# Encoder.net
KiCad netlist of a schematic drawn in Altium Designer
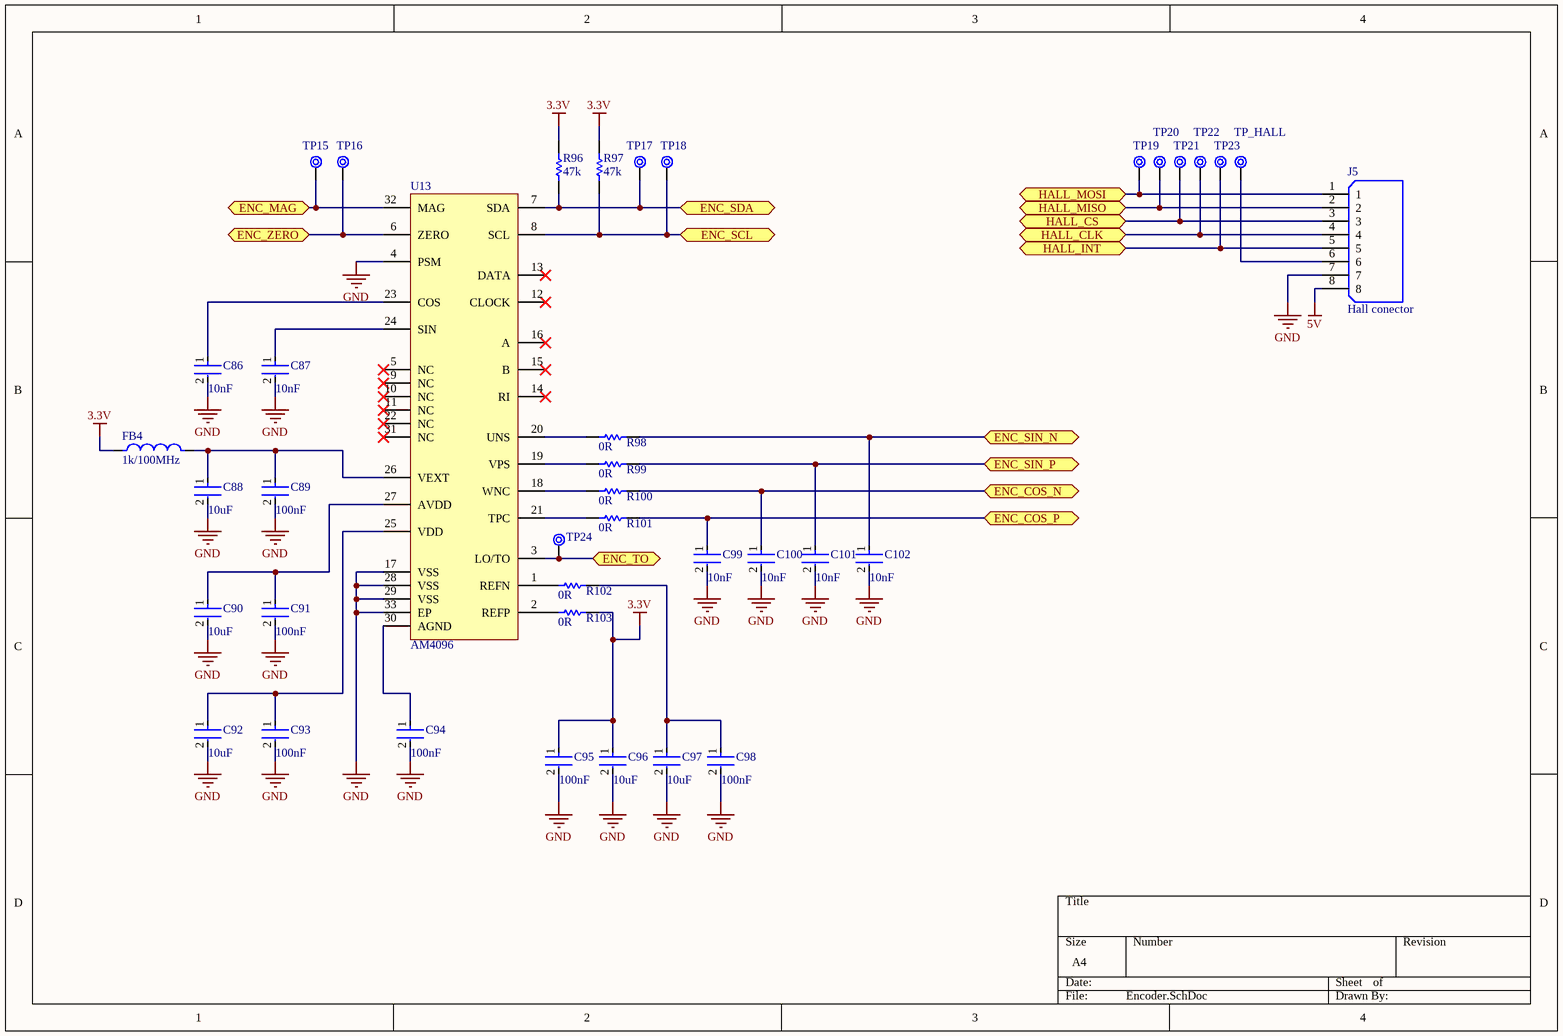
[diagram p0: Encoder.SchDoc]

(export (version "E")
  (design (tool "Eeschema 10.0.6"))
  (components
    (comp (ref "C86")
      (value "10nF")
      (footprint "FP-C0805C-DN-MFG")
      (description "CAP CER 0.1UF 50V X7R 0805")
      (fields
        (field (name "MANUFACTURER PART NUMBER") "C0805C104K5RACTU")
        (field (name "MANUFACTURER") "KEMET")
      )
      (libsource (lib "Altium Content Vault") (part "b4654b650e69147ec39a6b967a45e02"))
    )
    (comp (ref "C87")
      (value "10nF")
      (footprint "FP-C0805C-DN-MFG")
      (description "CAP CER 0.1UF 50V X7R 0805")
      (fields
        (field (name "MANUFACTURER PART NUMBER") "C0805C104K5RACTU")
        (field (name "MANUFACTURER") "KEMET")
      )
      (libsource (lib "Altium Content Vault") (part "b4654b650e69147ec39a6b967a45e02"))
    )
    (comp (ref "C88")
      (value "10uF")
      (footprint "FP-C0805C-DN-MFG")
      (description "CAP CER 0.1UF 50V X7R 0805")
      (fields
        (field (name "MANUFACTURER PART NUMBER") "C0805C104K5RACTU")
        (field (name "MANUFACTURER") "KEMET")
      )
      (libsource (lib "Altium Content Vault") (part "b4654b650e69147ec39a6b967a45e02"))
    )
    (comp (ref "C89")
      (value "100nF")
      (footprint "FP-C0805C-DN-MFG")
      (description "CAP CER 0.1UF 50V X7R 0805")
      (fields
        (field (name "MANUFACTURER PART NUMBER") "C0805C104K5RACTU")
        (field (name "MANUFACTURER") "KEMET")
      )
      (libsource (lib "Altium Content Vault") (part "b4654b650e69147ec39a6b967a45e02"))
    )
    (comp (ref "C90")
      (value "10uF")
      (footprint "FP-C0805C-DN-MFG")
      (description "CAP CER 0.1UF 50V X7R 0805")
      (fields
        (field (name "MANUFACTURER PART NUMBER") "C0805C104K5RACTU")
        (field (name "MANUFACTURER") "KEMET")
      )
      (libsource (lib "Altium Content Vault") (part "b4654b650e69147ec39a6b967a45e02"))
    )
    (comp (ref "C91")
      (value "100nF")
      (footprint "FP-C0805C-DN-MFG")
      (description "CAP CER 0.1UF 50V X7R 0805")
      (fields
        (field (name "MANUFACTURER PART NUMBER") "C0805C104K5RACTU")
        (field (name "MANUFACTURER") "KEMET")
      )
      (libsource (lib "Altium Content Vault") (part "b4654b650e69147ec39a6b967a45e02"))
    )
    (comp (ref "C92")
      (value "10uF")
      (footprint "FP-C0805C-DN-MFG")
      (description "CAP CER 0.1UF 50V X7R 0805")
      (fields
        (field (name "MANUFACTURER PART NUMBER") "C0805C104K5RACTU")
        (field (name "MANUFACTURER") "KEMET")
      )
      (libsource (lib "Altium Content Vault") (part "b4654b650e69147ec39a6b967a45e02"))
    )
    (comp (ref "C93")
      (value "100nF")
      (footprint "FP-C0805C-DN-MFG")
      (description "CAP CER 0.1UF 50V X7R 0805")
      (fields
        (field (name "MANUFACTURER PART NUMBER") "C0805C104K5RACTU")
        (field (name "MANUFACTURER") "KEMET")
      )
      (libsource (lib "Altium Content Vault") (part "b4654b650e69147ec39a6b967a45e02"))
    )
    (comp (ref "C94")
      (value "100nF")
      (footprint "FP-C0805C-DN-MFG")
      (description "CAP CER 0.1UF 50V X7R 0805")
      (fields
        (field (name "MANUFACTURER PART NUMBER") "C0805C104K5RACTU")
        (field (name "MANUFACTURER") "KEMET")
      )
      (libsource (lib "Altium Content Vault") (part "b4654b650e69147ec39a6b967a45e02"))
    )
    (comp (ref "C95")
      (value "100nF")
      (footprint "FP-C0805C-DN-MFG")
      (description "CAP CER 0.1UF 50V X7R 0805")
      (fields
        (field (name "MANUFACTURER PART NUMBER") "C0805C104K5RACTU")
        (field (name "MANUFACTURER") "KEMET")
      )
      (libsource (lib "Altium Content Vault") (part "b4654b650e69147ec39a6b967a45e02"))
    )
    (comp (ref "C96")
      (value "10uF")
      (footprint "FP-C0805C-DN-MFG")
      (description "CAP CER 0.1UF 50V X7R 0805")
      (fields
        (field (name "MANUFACTURER PART NUMBER") "C0805C104K5RACTU")
        (field (name "MANUFACTURER") "KEMET")
      )
      (libsource (lib "Altium Content Vault") (part "b4654b650e69147ec39a6b967a45e02"))
    )
    (comp (ref "C97")
      (value "10uF")
      (footprint "FP-C0805C-DN-MFG")
      (description "CAP CER 0.1UF 50V X7R 0805")
      (fields
        (field (name "MANUFACTURER PART NUMBER") "C0805C104K5RACTU")
        (field (name "MANUFACTURER") "KEMET")
      )
      (libsource (lib "Altium Content Vault") (part "b4654b650e69147ec39a6b967a45e02"))
    )
    (comp (ref "C98")
      (value "100nF")
      (footprint "FP-C0805C-DN-MFG")
      (description "CAP CER 0.1UF 50V X7R 0805")
      (fields
        (field (name "MANUFACTURER PART NUMBER") "C0805C104K5RACTU")
        (field (name "MANUFACTURER") "KEMET")
      )
      (libsource (lib "Altium Content Vault") (part "b4654b650e69147ec39a6b967a45e02"))
    )
    (comp (ref "C99")
      (value "10nF")
      (footprint "FP-C0805C-DN-MFG")
      (description "CAP CER 0.1UF 50V X7R 0805")
      (fields
        (field (name "MANUFACTURER PART NUMBER") "C0805C104K5RACTU")
        (field (name "MANUFACTURER") "KEMET")
      )
      (libsource (lib "Altium Content Vault") (part "b4654b650e69147ec39a6b967a45e02"))
    )
    (comp (ref "C100")
      (value "10nF")
      (footprint "FP-C0805C-DN-MFG")
      (description "CAP CER 0.1UF 50V X7R 0805")
      (fields
        (field (name "MANUFACTURER PART NUMBER") "C0805C104K5RACTU")
        (field (name "MANUFACTURER") "KEMET")
      )
      (libsource (lib "Altium Content Vault") (part "b4654b650e69147ec39a6b967a45e02"))
    )
    (comp (ref "C101")
      (value "10nF")
      (footprint "FP-C0805C-DN-MFG")
      (description "CAP CER 0.1UF 50V X7R 0805")
      (fields
        (field (name "MANUFACTURER PART NUMBER") "C0805C104K5RACTU")
        (field (name "MANUFACTURER") "KEMET")
      )
      (libsource (lib "Altium Content Vault") (part "b4654b650e69147ec39a6b967a45e02"))
    )
    (comp (ref "C102")
      (value "10nF")
      (footprint "FP-C0805C-DN-MFG")
      (description "CAP CER 0.1UF 50V X7R 0805")
      (fields
        (field (name "MANUFACTURER PART NUMBER") "C0805C104K5RACTU")
        (field (name "MANUFACTURER") "KEMET")
      )
      (libsource (lib "Altium Content Vault") (part "b4654b650e69147ec39a6b967a45e02"))
    )
    (comp (ref "FB4")
      (value "1k/100MHz")
      (footprint "FB_0603")
      (description "Ferrite Beads 1K OHM 25%")
      (fields (field (name "MANUFACTURER") "TDK") (field (name "PART NUMBER") "MMZ1608B102CTA00"))
      (libsource (lib "INDUCTOR") (part "FB/MMZ1608B102CTA00"))
    )
    (comp (ref "J5")
      (value "Hall conector")
      (footprint "AMPHENOL_10114830-11108LF")
      (description "1.25mm Wire to Board Wafer, Right Angle, Surface Mount, 8 Positions")
      (fields (field (name "MF") "Amphenol ICC") (field (name "MP") "10114830-11108LF"))
      (libsource (lib "10114830-11108LF") (part "10114830-11108LF"))
    )
    (comp (ref "R96")
      (value "47k")
      (footprint "RESC2013X50X30LL20T20")
      (fields (field (name "MANUFACTURER") "Vishay Dale") (field (name "PART NUMBER") "CRCW08050000Z0EA"))
      (libsource (lib "Altium Content Vault") (part "RES"))
    )
    (comp (ref "R97")
      (value "47k")
      (footprint "RESC2013X50X30LL20T20")
      (fields (field (name "MANUFACTURER") "Vishay Dale") (field (name "PART NUMBER") "CRCW08050000Z0EA"))
      (libsource (lib "Altium Content Vault") (part "RES"))
    )
    (comp (ref "R98")
      (value "0R")
      (footprint "RESC1609X50X30NL8T20")
      (description "Chip Resistor, 0 Ohm, Jumper, 100 mW, -55 to 155 degC, 0603 (1608 Metric), RoHS, Tape and Reel")
      (fields (field (name "MANUFACTURER") "Vishay Semiconductor"))
      (libsource (lib "Altium Content Vault") (part "RES-2"))
    )
    (comp (ref "R99")
      (value "0R")
      (footprint "RESC1609X50X30NL8T20")
      (description "Chip Resistor, 0 Ohm, Jumper, 100 mW, -55 to 155 degC, 0603 (1608 Metric), RoHS, Tape and Reel")
      (fields (field (name "MANUFACTURER") "Vishay Semiconductor"))
      (libsource (lib "Altium Content Vault") (part "RES-2"))
    )
    (comp (ref "R100")
      (value "0R")
      (footprint "RESC1609X50X30NL8T20")
      (description "Chip Resistor, 0 Ohm, Jumper, 100 mW, -55 to 155 degC, 0603 (1608 Metric), RoHS, Tape and Reel")
      (fields (field (name "MANUFACTURER") "Vishay Semiconductor"))
      (libsource (lib "Altium Content Vault") (part "RES-2"))
    )
    (comp (ref "R101")
      (value "0R")
      (footprint "RESC1609X50X30NL8T20")
      (description "Chip Resistor, 0 Ohm, Jumper, 100 mW, -55 to 155 degC, 0603 (1608 Metric), RoHS, Tape and Reel")
      (fields (field (name "MANUFACTURER") "Vishay Semiconductor"))
      (libsource (lib "Altium Content Vault") (part "RES-2"))
    )
    (comp (ref "R102")
      (value "0R")
      (footprint "RESC1609X50X30NL8T20")
      (description "Chip Resistor, 0 Ohm, Jumper, 100 mW, -55 to 155 degC, 0603 (1608 Metric), RoHS, Tape and Reel")
      (fields (field (name "MANUFACTURER") "Vishay Semiconductor"))
      (libsource (lib "Altium Content Vault") (part "RES-2"))
    )
    (comp (ref "R103")
      (value "0R")
      (footprint "RESC1609X50X30NL8T20")
      (description "Chip Resistor, 0 Ohm, Jumper, 100 mW, -55 to 155 degC, 0603 (1608 Metric), RoHS, Tape and Reel")
      (fields (field (name "MANUFACTURER") "Vishay Semiconductor"))
      (libsource (lib "Altium Content Vault") (part "RES-2"))
    )
    (comp (ref "TP15")
      (value "Test Point 1mm")
      (footprint "Pad 1mm")
      (libsource (lib "OTHER") (part "Test Point 1mm"))
    )
    (comp (ref "TP16")
      (value "Test Point 1mm")
      (footprint "Pad 1mm")
      (libsource (lib "OTHER") (part "Test Point 1mm"))
    )
    (comp (ref "TP17")
      (value "Test Point 1mm")
      (footprint "Pad 1mm")
      (libsource (lib "OTHER") (part "Test Point 1mm"))
    )
    (comp (ref "TP18")
      (value "Test Point 1mm")
      (footprint "Pad 1mm")
      (libsource (lib "OTHER") (part "Test Point 1mm"))
    )
    (comp (ref "TP19")
      (value "Test Point 1mm")
      (footprint "Pad 1mm")
      (libsource (lib "OTHER") (part "Test Point 1mm"))
    )
    (comp (ref "TP20")
      (value "Test Point 1mm")
      (footprint "Pad 1mm")
      (libsource (lib "OTHER") (part "Test Point 1mm"))
    )
    (comp (ref "TP21")
      (value "Test Point 1mm")
      (footprint "Pad 1mm")
      (libsource (lib "OTHER") (part "Test Point 1mm"))
    )
    (comp (ref "TP22")
      (value "Test Point 1mm")
      (footprint "Pad 1mm")
      (libsource (lib "OTHER") (part "Test Point 1mm"))
    )
    (comp (ref "TP23")
      (value "Test Point 1mm")
      (footprint "Pad 1mm")
      (libsource (lib "OTHER") (part "Test Point 1mm"))
    )
    (comp (ref "TP24")
      (value "Test Point 1mm")
      (footprint "Pad 1mm")
      (libsource (lib "OTHER") (part "Test Point 1mm"))
    )
    (comp (ref "TP_HALL")
      (value "Test Point 1mm")
      (footprint "Pad 1mm")
      (libsource (lib "OTHER") (part "Test Point 1mm"))
    )
    (comp (ref "U13")
      (value "AM4096")
      (footprint "QFN65P600X600X100_HS-33N")
      (description "12 bit Rotary Magnetic Encoder IC")
      (fields (field (name "MANUFACTURER") "RLS"))
      (libsource (lib "IC") (part "AM4096"))
    )
  )
  (nets
    (net (code "1") (name "/ENC_COS_N") (class "Default")
      (node (ref "C100") (pin "1") (pinfunction "1_1") (pintype "passive"))
      (node (ref "R100") (pin "2") (pinfunction "2_2") (pintype "passive"))
    )
    (net (code "2") (name "/ENC_COS_P") (class "Default")
      (node (ref "C99") (pin "1") (pinfunction "1_1") (pintype "passive"))
      (node (ref "R101") (pin "2") (pinfunction "2_2") (pintype "passive"))
    )
    (net (code "3") (name "/ENC_MAG") (class "Default")
      (node (ref "TP15") (pin "1") (pinfunction "1_1") (pintype "passive"))
      (node (ref "U13") (pin "32") (pinfunction "MAG_32") (pintype "passive"))
    )
    (net (code "4") (name "/ENC_SCL") (class "Default")
      (node (ref "R97") (pin "1") (pinfunction "1_1") (pintype "passive"))
      (node (ref "TP18") (pin "1") (pinfunction "1_1") (pintype "passive"))
      (node (ref "U13") (pin "8") (pinfunction "SCL_8") (pintype "passive"))
    )
    (net (code "5") (name "/ENC_SDA") (class "Default")
      (node (ref "R96") (pin "1") (pinfunction "1_1") (pintype "passive"))
      (node (ref "TP17") (pin "1") (pinfunction "1_1") (pintype "passive"))
      (node (ref "U13") (pin "7") (pinfunction "SDA_7") (pintype "passive"))
    )
    (net (code "6") (name "/ENC_SIN_N") (class "Default")
      (node (ref "C102") (pin "1") (pinfunction "1_1") (pintype "passive"))
      (node (ref "R98") (pin "2") (pinfunction "2_2") (pintype "passive"))
    )
    (net (code "7") (name "/ENC_SIN_P") (class "Default")
      (node (ref "C101") (pin "1") (pinfunction "1_1") (pintype "passive"))
      (node (ref "R99") (pin "2") (pinfunction "2_2") (pintype "passive"))
    )
    (net (code "8") (name "/ENC_TO") (class "Default")
      (node (ref "TP24") (pin "1") (pinfunction "1_1") (pintype "passive"))
      (node (ref "U13") (pin "3") (pinfunction "LO/TO_3") (pintype "passive"))
    )
    (net (code "9") (name "/ENC_ZERO") (class "Default")
      (node (ref "TP16") (pin "1") (pinfunction "1_1") (pintype "passive"))
      (node (ref "U13") (pin "6") (pinfunction "ZERO_6") (pintype "passive"))
    )
    (net (code "10") (name "/HALL_CLK") (class "Default")
      (node (ref "J5") (pin "4") (pinfunction "4_4") (pintype "passive"))
      (node (ref "TP22") (pin "1") (pinfunction "1_1") (pintype "passive"))
    )
    (net (code "11") (name "/HALL_CS") (class "Default")
      (node (ref "J5") (pin "3") (pinfunction "3_3") (pintype "passive"))
      (node (ref "TP21") (pin "1") (pinfunction "1_1") (pintype "passive"))
    )
    (net (code "12") (name "/HALL_INT") (class "Default")
      (node (ref "J5") (pin "5") (pinfunction "5_5") (pintype "passive"))
      (node (ref "TP23") (pin "1") (pinfunction "1_1") (pintype "passive"))
    )
    (net (code "13") (name "/HALL_MISO") (class "Default")
      (node (ref "J5") (pin "2") (pinfunction "2_2") (pintype "passive"))
      (node (ref "TP20") (pin "1") (pinfunction "1_1") (pintype "passive"))
    )
    (net (code "14") (name "/HALL_MOSI") (class "Default")
      (node (ref "J5") (pin "1") (pinfunction "1_1") (pintype "passive"))
      (node (ref "TP19") (pin "1") (pinfunction "1_1") (pintype "passive"))
    )
    (net (code "15") (name "3.3V") (class "Default")
      (node (ref "C95") (pin "1") (pinfunction "1_1") (pintype "passive"))
      (node (ref "C96") (pin "1") (pinfunction "1_1") (pintype "passive"))
      (node (ref "FB4") (pin "1") (pinfunction "1_1") (pintype "passive"))
      (node (ref "R103") (pin "2") (pinfunction "2_2") (pintype "passive"))
      (node (ref "R96") (pin "2") (pinfunction "2_2") (pintype "passive"))
      (node (ref "R97") (pin "2") (pinfunction "2_2") (pintype "passive"))
    )
    (net (code "16") (name "5V") (class "Default")
      (node (ref "J5") (pin "8") (pinfunction "8_8") (pintype "passive"))
    )
    (net (code "17") (name "GND") (class "Default")
      (node (ref "C100") (pin "2") (pinfunction "2_2") (pintype "passive"))
      (node (ref "C101") (pin "2") (pinfunction "2_2") (pintype "passive"))
      (node (ref "C102") (pin "2") (pinfunction "2_2") (pintype "passive"))
      (node (ref "C86") (pin "2") (pinfunction "2_2") (pintype "passive"))
      (node (ref "C87") (pin "2") (pinfunction "2_2") (pintype "passive"))
      (node (ref "C88") (pin "2") (pinfunction "2_2") (pintype "passive"))
      (node (ref "C89") (pin "2") (pinfunction "2_2") (pintype "passive"))
      (node (ref "C90") (pin "2") (pinfunction "2_2") (pintype "passive"))
      (node (ref "C91") (pin "2") (pinfunction "2_2") (pintype "passive"))
      (node (ref "C92") (pin "2") (pinfunction "2_2") (pintype "passive"))
      (node (ref "C93") (pin "2") (pinfunction "2_2") (pintype "passive"))
      (node (ref "C94") (pin "2") (pinfunction "2_2") (pintype "passive"))
      (node (ref "C95") (pin "2") (pinfunction "2_2") (pintype "passive"))
      (node (ref "C96") (pin "2") (pinfunction "2_2") (pintype "passive"))
      (node (ref "C97") (pin "2") (pinfunction "2_2") (pintype "passive"))
      (node (ref "C98") (pin "2") (pinfunction "2_2") (pintype "passive"))
      (node (ref "C99") (pin "2") (pinfunction "2_2") (pintype "passive"))
      (node (ref "J5") (pin "7") (pinfunction "7_7") (pintype "passive"))
      (node (ref "U13") (pin "17") (pinfunction "VSS_17") (pintype "passive"))
      (node (ref "U13") (pin "28") (pinfunction "VSS_28") (pintype "passive"))
      (node (ref "U13") (pin "29") (pinfunction "VSS_29") (pintype "passive"))
      (node (ref "U13") (pin "33") (pinfunction "EP_33") (pintype "passive"))
      (node (ref "U13") (pin "4") (pinfunction "PSM_4") (pintype "passive"))
    )
    (net (code "18") (name "Net-(C97-Pad1)") (class "Default")
      (node (ref "C97") (pin "1") (pinfunction "1_1") (pintype "passive"))
      (node (ref "C98") (pin "1") (pinfunction "1_1") (pintype "passive"))
      (node (ref "R102") (pin "2") (pinfunction "2_2") (pintype "passive"))
    )
    (net (code "19") (name "Net-(J5-Pad6)") (class "Default")
      (node (ref "J5") (pin "6") (pinfunction "6_6") (pintype "passive"))
      (node (ref "TP_HALL") (pin "1") (pinfunction "1_1") (pintype "passive"))
    )
    (net (code "20") (name "Net-(U13-AGND)") (class "Default")
      (node (ref "C94") (pin "1") (pinfunction "1_1") (pintype "passive"))
      (node (ref "U13") (pin "30") (pinfunction "AGND_30") (pintype "passive"))
    )
    (net (code "21") (name "Net-(U13-AVDD)") (class "Default")
      (node (ref "C90") (pin "1") (pinfunction "1_1") (pintype "passive"))
      (node (ref "C91") (pin "1") (pinfunction "1_1") (pintype "passive"))
      (node (ref "U13") (pin "27") (pinfunction "AVDD_27") (pintype "passive"))
    )
    (net (code "22") (name "Net-(U13-COS)") (class "Default")
      (node (ref "C86") (pin "1") (pinfunction "1_1") (pintype "passive"))
      (node (ref "U13") (pin "23") (pinfunction "COS_23") (pintype "passive"))
    )
    (net (code "23") (name "Net-(U13-REFN)") (class "Default")
      (node (ref "R102") (pin "1") (pinfunction "1_1") (pintype "passive"))
      (node (ref "U13") (pin "1") (pinfunction "REFN_1") (pintype "passive"))
    )
    (net (code "24") (name "Net-(U13-REFP)") (class "Default")
      (node (ref "R103") (pin "1") (pinfunction "1_1") (pintype "passive"))
      (node (ref "U13") (pin "2") (pinfunction "REFP_2") (pintype "passive"))
    )
    (net (code "25") (name "Net-(U13-SIN)") (class "Default")
      (node (ref "C87") (pin "1") (pinfunction "1_1") (pintype "passive"))
      (node (ref "U13") (pin "24") (pinfunction "SIN_24") (pintype "passive"))
    )
    (net (code "26") (name "Net-(U13-TPC)") (class "Default")
      (node (ref "R101") (pin "1") (pinfunction "1_1") (pintype "passive"))
      (node (ref "U13") (pin "21") (pinfunction "TPC_21") (pintype "passive"))
    )
    (net (code "27") (name "Net-(U13-UNS)") (class "Default")
      (node (ref "R98") (pin "1") (pinfunction "1_1") (pintype "passive"))
      (node (ref "U13") (pin "20") (pinfunction "UNS_20") (pintype "passive"))
    )
    (net (code "28") (name "Net-(U13-VDD)") (class "Default")
      (node (ref "C92") (pin "1") (pinfunction "1_1") (pintype "passive"))
      (node (ref "C93") (pin "1") (pinfunction "1_1") (pintype "passive"))
      (node (ref "U13") (pin "25") (pinfunction "VDD_25") (pintype "passive"))
    )
    (net (code "29") (name "Net-(U13-VEXT)") (class "Default")
      (node (ref "C88") (pin "1") (pinfunction "1_1") (pintype "passive"))
      (node (ref "C89") (pin "1") (pinfunction "1_1") (pintype "passive"))
      (node (ref "FB4") (pin "2") (pinfunction "2_2") (pintype "passive"))
      (node (ref "U13") (pin "26") (pinfunction "VEXT_26") (pintype "passive"))
    )
    (net (code "30") (name "Net-(U13-VPS)") (class "Default")
      (node (ref "R99") (pin "1") (pinfunction "1_1") (pintype "passive"))
      (node (ref "U13") (pin "19") (pinfunction "VPS_19") (pintype "passive"))
    )
    (net (code "31") (name "Net-(U13-WNC)") (class "Default")
      (node (ref "R100") (pin "1") (pinfunction "1_1") (pintype "passive"))
      (node (ref "U13") (pin "18") (pinfunction "WNC_18") (pintype "passive"))
    )
    (net (code "32") (name "unconnected-(U13-A-Pad16)") (class "Default")
      (node (ref "U13") (pin "16") (pinfunction "A_16") (pintype "passive+no_connect"))
    )
    (net (code "33") (name "unconnected-(U13-B-Pad15)") (class "Default")
      (node (ref "U13") (pin "15") (pinfunction "B_15") (pintype "passive+no_connect"))
    )
    (net (code "34") (name "unconnected-(U13-CLOCK-Pad12)") (class "Default")
      (node (ref "U13") (pin "12") (pinfunction "CLOCK_12") (pintype "passive+no_connect"))
    )
    (net (code "35") (name "unconnected-(U13-DATA-Pad13)") (class "Default")
      (node (ref "U13") (pin "13") (pinfunction "DATA_13") (pintype "passive+no_connect"))
    )
    (net (code "36") (name "unconnected-(U13-NC-Pad5)") (class "Default")
      (node (ref "U13") (pin "5") (pinfunction "NC_5") (pintype "passive+no_connect"))
    )
    (net (code "37") (name "unconnected-(U13-NC-Pad9)") (class "Default")
      (node (ref "U13") (pin "9") (pinfunction "NC_9") (pintype "passive+no_connect"))
    )
    (net (code "38") (name "unconnected-(U13-NC-Pad10)") (class "Default")
      (node (ref "U13") (pin "10") (pinfunction "NC_10") (pintype "passive+no_connect"))
    )
    (net (code "39") (name "unconnected-(U13-NC-Pad11)") (class "Default")
      (node (ref "U13") (pin "11") (pinfunction "NC_11") (pintype "passive+no_connect"))
    )
    (net (code "40") (name "unconnected-(U13-NC-Pad22)") (class "Default")
      (node (ref "U13") (pin "22") (pinfunction "NC_22") (pintype "passive+no_connect"))
    )
    (net (code "41") (name "unconnected-(U13-NC-Pad31)") (class "Default")
      (node (ref "U13") (pin "31") (pinfunction "NC_31") (pintype "passive+no_connect"))
    )
    (net (code "42") (name "unconnected-(U13-RI-Pad14)") (class "Default")
      (node (ref "U13") (pin "14") (pinfunction "RI_14") (pintype "passive+no_connect"))
    )
  )
)
